# doorLock_schematic.net
KiCad netlist of a schematic drawn in Altium Designer
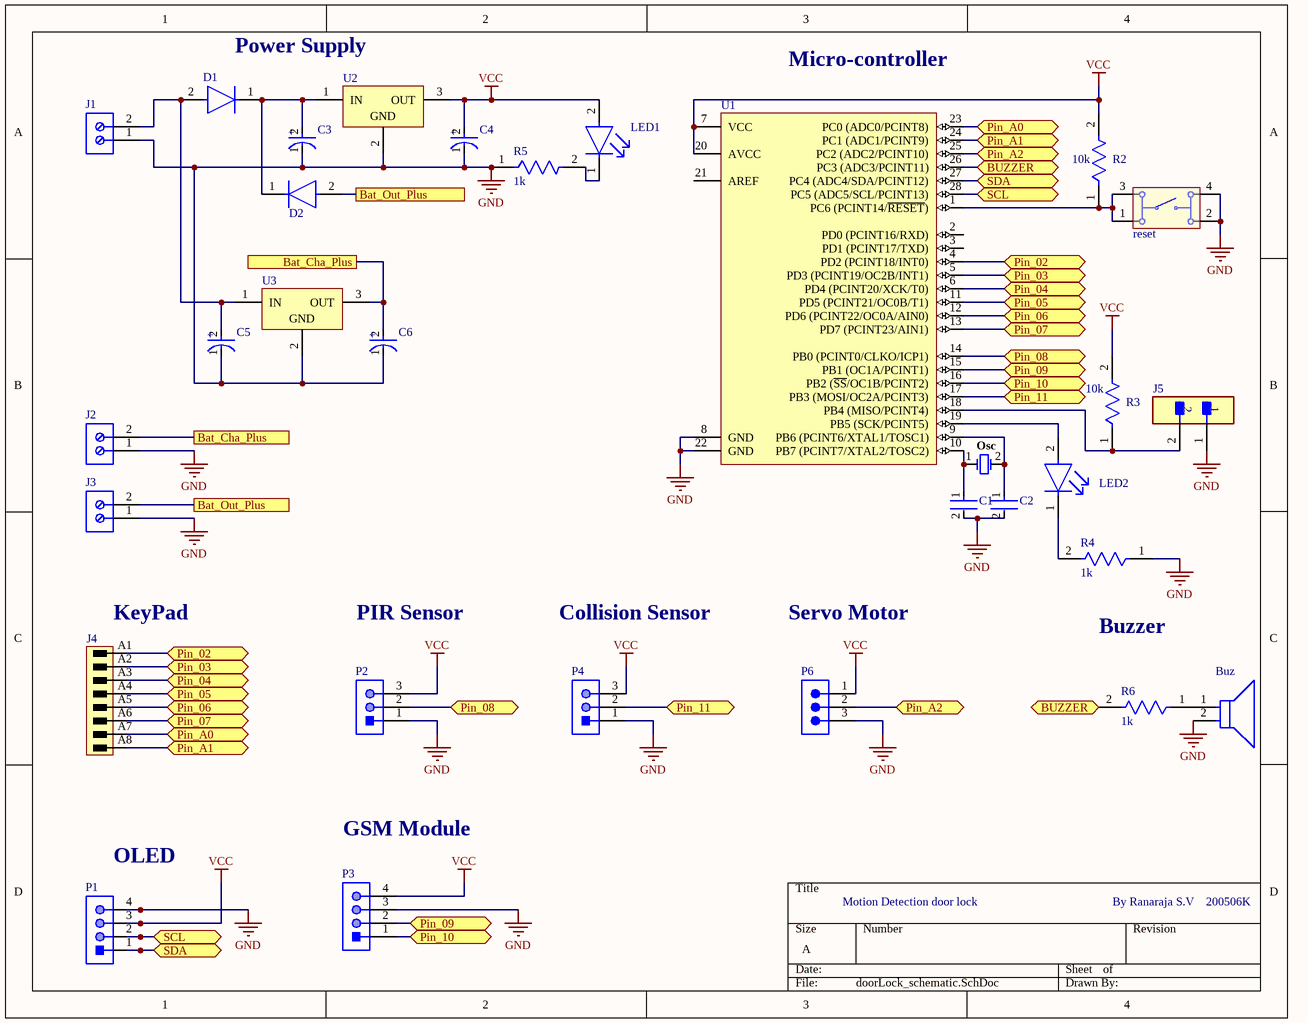
[diagram p0: doorLock_schematic.SchDoc]

(export (version "E")
  (design (tool "Eeschema 10.0.6"))
  (components
    (comp (ref "Buz")
      (value "SD1614TT-B3M")
      (footprint "FP-SD1614TT-B3M-MFG")
      (description "AUDIO MAGNETIC XDCR 6-16V TH")
      (libsource (lib "Altium Content Vault") (part "1973c4b650225fd2ddacaff6b763965"))
    )
    (comp (ref "C1")
      (value "RCE5C2A220J0DBH03A")
      (footprint "FP-RCE0DB-MFG")
      (description "Cap Ceramic 22pF 100V C0G ±5% Radial 2.5mm +125°C Ammo Pack")
      (fields (field (name "VOLTAGE") "100V") (field (name "TOLERANCE") "5%"))
      (libsource (lib "Altium Content Vault") (part "b4654b650e69147ec39a6b967a45e02"))
    )
    (comp (ref "C2")
      (value "RCE5C2A220J0DBH03A")
      (footprint "FP-RCE0DB-MFG")
      (description "Cap Ceramic 22pF 100V C0G ±5% Radial 2.5mm +125°C Ammo Pack")
      (fields (field (name "VOLTAGE") "100V") (field (name "TOLERANCE") "5%"))
      (libsource (lib "Altium Content Vault") (part "b4654b650e69147ec39a6b967a45e02"))
    )
    (comp (ref "C3")
      (value "EEUFC1V151")
      (footprint "FP-RAD-TH-D_8_0_5-L_11_5-MFG")
      (description "Aluminum Electrolytic Capacitors (Radial Lead Type) AEC-Q200 Qualified 150uF ±20% 35V")
      (fields (field (name "VOLTAGE") "35V") (field (name "TOLERANCE") "20%"))
      (libsource (lib "Altium Content Vault") (part "203bc49f2ac43e59fd269a8c329ed05"))
    )
    (comp (ref "C4")
      (value "EEUFC1V151")
      (footprint "FP-RAD-TH-D_8_0_5-L_11_5-MFG")
      (description "Aluminum Electrolytic Capacitors (Radial Lead Type) AEC-Q200 Qualified 150uF ±20% 35V")
      (fields (field (name "VOLTAGE") "35V") (field (name "TOLERANCE") "20%"))
      (libsource (lib "Altium Content Vault") (part "203bc49f2ac43e59fd269a8c329ed05"))
    )
    (comp (ref "C5")
      (value "EEUFC1V151")
      (footprint "FP-RAD-TH-D_8_0_5-L_11_5-MFG")
      (description "Aluminum Electrolytic Capacitors (Radial Lead Type) AEC-Q200 Qualified 150uF ±20% 35V")
      (fields (field (name "VOLTAGE") "35V") (field (name "TOLERANCE") "20%"))
      (libsource (lib "Altium Content Vault") (part "203bc49f2ac43e59fd269a8c329ed05"))
    )
    (comp (ref "C6")
      (value "EEUFC1V151")
      (footprint "FP-RAD-TH-D_8_0_5-L_11_5-MFG")
      (description "Aluminum Electrolytic Capacitors (Radial Lead Type) AEC-Q200 Qualified 150uF ±20% 35V")
      (fields (field (name "VOLTAGE") "35V") (field (name "TOLERANCE") "20%"))
      (libsource (lib "Altium Content Vault") (part "203bc49f2ac43e59fd269a8c329ed05"))
    )
    (comp (ref "D1")
      (value "1N4007")
      (footprint "FP-1N4007-MFG")
      (description "Rectifier diode 1000 V 1 A DO-41, ,")
      (fields
        (field (name "MANUFACTURER") "Diotec")
        (field (name "OCTOPART") "https://octopart.com/1n4007-diotec-4040411")
      )
      (libsource (lib "Altium Content Vault") (part "d7152d700b627762746794eb795d46e"))
    )
    (comp (ref "D2")
      (value "1N4007")
      (footprint "FP-1N4007-MFG")
      (description "Rectifier diode 1000 V 1 A DO-41, ,")
      (fields
        (field (name "MANUFACTURER") "Diotec")
        (field (name "OCTOPART") "https://octopart.com/1n4007-diotec-4040411")
      )
      (libsource (lib "Altium Content Vault") (part "d7152d700b627762746794eb795d46e"))
    )
    (comp (ref "J1")
      (value "691102710002")
      (footprint "691102710002")
      (description "Series 102 - 5.00 mm Horizontal Entry Modular with Pressure Clamp WR-TBL, 2 pin")
      (fields (field (name "MANUFACTURER") "Wurth Elektronik") (field (name "PUBLISHER") "WurthElektronik"))
      (libsource (lib "Altium Content Vault") (part "WE-CN-1P-F-TB2"))
    )
    (comp (ref "J2")
      (value "691102710002")
      (footprint "691102710002")
      (description "Series 102 - 5.00 mm Horizontal Entry Modular with Pressure Clamp WR-TBL, 2 pin")
      (fields (field (name "MANUFACTURER") "Wurth Elektronik") (field (name "PUBLISHER") "WurthElektronik"))
      (libsource (lib "Altium Content Vault") (part "WE-CN-1P-F-TB2"))
    )
    (comp (ref "J3")
      (value "691102710002")
      (footprint "691102710002")
      (description "Series 102 - 5.00 mm Horizontal Entry Modular with Pressure Clamp WR-TBL, 2 pin")
      (fields (field (name "MANUFACTURER") "Wurth Elektronik") (field (name "PUBLISHER") "WurthElektronik"))
      (libsource (lib "Altium Content Vault") (part "WE-CN-1P-F-TB2"))
    )
    (comp (ref "J4")
      (value "1842380000")
      (footprint "SL_SMT_3_5_180G_08")
      (description "OMNIMATE Signal - series BL/SL 3.50")
      (fields (field (name "MANUFACTURER") "Weidmueller"))
      (libsource (lib "Altium Content Vault") (part "Header_Male_08_1x08"))
    )
    (comp (ref "J5")
      (value "TSW-102-07-F-S")
      (footprint "FP-TSW-102-07-F-S-MFG")
      (description "CONN HEADER VERT 2POS 2.54MM")
      (libsource (lib "Altium Content Vault") (part "3bc925449376181038e59eaffc5286c"))
    )
    (comp (ref "LED1")
      (value "LG L29K-G2J1-24-Z")
      (footprint "FP-LG_L29K-MFG")
      (description "LED GREEN DIFFUSED 0603 SMD")
      (libsource (lib "Altium Content Vault") (part "8706943c75ba83719d021d2fdc84c58"))
    )
    (comp (ref "LED2")
      (value "LG L29K-G2J1-24-Z")
      (footprint "FP-LG_L29K-MFG")
      (description "LED GREEN DIFFUSED 0603 SMD")
      (libsource (lib "Altium Content Vault") (part "8706943c75ba83719d021d2fdc84c58"))
    )
    (comp (ref "Osc")
      (value "FOXSLF/160-20")
      (footprint "FOX-FOXSLF160-20")
      (description "Resistance Weld Thru-Hole Crystal, 16 MHz, -20 to 70 degC, 2-Pin THD, RoHS, Bulk")
      (fields (field (name "TOLERANCE") "1%"))
      (libsource (lib "Altium Content Vault") (part "XTAL-1-2-2"))
    )
    (comp (ref "P1")
      (value "691311700104")
      (footprint "691311700104")
      (description "Serie 3117 - 5.00mm Close Vertical PCB Header WR-TBL, 4 pin")
      (fields (field (name "MANUFACTURER") "Wurth Elektronik") (field (name "PUBLISHER") "WurthElektronik"))
      (libsource (lib "Altium Content Vault") (part "WE-CN-1P-M-R4"))
    )
    (comp (ref "P2")
      (value "691322110003")
      (footprint "691322110003")
      (description "Serie 3221 - 3.50mm Horizontal PCB Header WR-TBL, 3 pin")
      (fields (field (name "MANUFACTURER") "Wurth Elektronik") (field (name "PUBLISHER") "WurthElektronik"))
      (libsource (lib "Altium Content Vault") (part "WE-CN-1P-M-R3"))
    )
    (comp (ref "P3")
      (value "691311700104")
      (footprint "691311700104")
      (description "Serie 3117 - 5.00mm Close Vertical PCB Header WR-TBL, 4 pin")
      (fields (field (name "MANUFACTURER") "Wurth Elektronik") (field (name "PUBLISHER") "WurthElektronik"))
      (libsource (lib "Altium Content Vault") (part "WE-CN-1P-M-R4"))
    )
    (comp (ref "P4")
      (value "691322110003")
      (footprint "691322110003")
      (description "Serie 3221 - 3.50mm Horizontal PCB Header WR-TBL, 3 pin")
      (fields (field (name "MANUFACTURER") "Wurth Elektronik") (field (name "PUBLISHER") "WurthElektronik"))
      (libsource (lib "Altium Content Vault") (part "WE-CN-1P-M-R3"))
    )
    (comp (ref "P6")
      (value "TSW-103-07-G-S")
      (footprint "SMTC-TSW-103-07-X-S")
      (description "0.025\" SQ Post Header, Through-hole, Vertical, -55 to 125 degC, 2.54 mm Pitch, 3-Pin, Male, RoHS")
      (fields (field (name "MANUFACTURER") "Samtec"))
      (libsource (lib "Altium Content Vault") (part "SMTC-TSW-103-X-X-S-X"))
    )
    (comp (ref "R2")
      (value "MRS16000C2002FCT00")
      (footprint "FP-MRS1600-MFG")
      (description "RES 20K OHM 0.4W 1% AXIAL")
      (fields (field (name "TOLERANCE") "1%") (field (name "RESISTANCE") "10k"))
      (libsource (lib "Altium Content Vault") (part "1029c3af85768c4190bb7ad29bc67b5"))
    )
    (comp (ref "R3")
      (value "MRS16000C2002FCT00")
      (footprint "FP-MRS1600-MFG")
      (description "RES 20K OHM 0.4W 1% AXIAL")
      (fields (field (name "TOLERANCE") "1%") (field (name "RESISTANCE") "10k"))
      (libsource (lib "Altium Content Vault") (part "1029c3af85768c4190bb7ad29bc67b5"))
    )
    (comp (ref "R4")
      (value "MRS16000C2002FCT00")
      (footprint "FP-MRS1600-MFG")
      (description "RES 20K OHM 0.4W 1% AXIAL")
      (fields (field (name "TOLERANCE") "1%") (field (name "RESISTANCE") "1k"))
      (libsource (lib "Altium Content Vault") (part "1029c3af85768c4190bb7ad29bc67b5"))
    )
    (comp (ref "R5")
      (value "MRS16000C2002FCT00")
      (footprint "FP-MRS1600-MFG")
      (description "RES 20K OHM 0.4W 1% AXIAL")
      (fields (field (name "TOLERANCE") "1%") (field (name "RESISTANCE") "1k"))
      (libsource (lib "Altium Content Vault") (part "1029c3af85768c4190bb7ad29bc67b5"))
    )
    (comp (ref "R6")
      (value "MRS16000C2002FCT00")
      (footprint "FP-MRS1600-MFG")
      (description "RES 20K OHM 0.4W 1% AXIAL")
      (fields (field (name "TOLERANCE") "1%") (field (name "RESISTANCE") "1k"))
      (libsource (lib "Altium Content Vault") (part "1029c3af85768c4190bb7ad29bc67b5"))
    )
    (comp (ref "reset")
      (value "430156043726")
      (footprint "430156043726")
      (description "WS-TATV THT Tact Switch 6X6 mm")
      (fields (field (name "MANUFACTURER") "Wuerth Elektronik"))
      (libsource (lib "Altium Content Vault") (part "WE-TACT-SW-4"))
    )
    (comp (ref "U1")
      (value "ATmega328-PU")
      (footprint "28P3")
      (libsource (lib "Altium Content Vault") (part "MC-8B-ATM48-IL28"))
    )
    (comp (ref "U2")
      (value "L7805CV")
      (footprint "TO220")
      (description "Positive Voltage Regulator, 5V, 3-Pin TO-220")
      (libsource (lib "Altium Content Vault") (part "PM-REG-L4940-SIL3"))
    )
    (comp (ref "U3")
      (value "L7805CV")
      (footprint "TO220")
      (description "Positive Voltage Regulator, 5V, 3-Pin TO-220")
      (libsource (lib "Altium Content Vault") (part "PM-REG-L4940-SIL3"))
    )
  )
  (nets
    (net (code "1") (name "/BUZZER") (class "Default")
      (node (ref "R6") (pin "2") (pinfunction "2_2") (pintype "passive"))
      (node (ref "U1") (pin "26") (pinfunction "PC3_(ADC3/PCINT11)_26") (pintype "bidirectional"))
    )
    (net (code "2") (name "/Bat_Cha_Plus") (class "Default")
      (node (ref "C6") (pin "2") (pinfunction "A_2") (pintype "passive"))
      (node (ref "J2") (pin "2") (pinfunction "2_2") (pintype "passive"))
      (node (ref "U3") (pin "3") (pinfunction "OUT_3") (pintype "power_in"))
    )
    (net (code "3") (name "/Bat_Out_Plus") (class "Default")
      (node (ref "D2") (pin "2") (pinfunction "A_2") (pintype "passive"))
      (node (ref "J3") (pin "2") (pinfunction "2_2") (pintype "passive"))
    )
    (net (code "4") (name "/Pin_02") (class "Default")
      (node (ref "J4") (pin "A1") (pinfunction "A1_A1") (pintype "passive"))
      (node (ref "U1") (pin "4") (pinfunction "PD2_(PCINT18/INT0)_4") (pintype "bidirectional"))
    )
    (net (code "5") (name "/Pin_03") (class "Default")
      (node (ref "J4") (pin "A2") (pinfunction "A2_A2") (pintype "passive"))
      (node (ref "U1") (pin "5") (pinfunction "PD3_(PCINT19/OC2B/INT1)_5") (pintype "bidirectional"))
    )
    (net (code "6") (name "/Pin_04") (class "Default")
      (node (ref "J4") (pin "A3") (pinfunction "A3_A3") (pintype "passive"))
      (node (ref "U1") (pin "6") (pinfunction "PD4_(PCINT20/XCK/T0)_6") (pintype "bidirectional"))
    )
    (net (code "7") (name "/Pin_05") (class "Default")
      (node (ref "J4") (pin "A4") (pinfunction "A4_A4") (pintype "passive"))
      (node (ref "U1") (pin "11") (pinfunction "PD5_(PCINT21/OC0B/T1)_11") (pintype "bidirectional"))
    )
    (net (code "8") (name "/Pin_06") (class "Default")
      (node (ref "J4") (pin "A5") (pinfunction "A5_A5") (pintype "passive"))
      (node (ref "U1") (pin "12") (pinfunction "PD6_(PCINT22/OC0A/AIN0)_12") (pintype "bidirectional"))
    )
    (net (code "9") (name "/Pin_07") (class "Default")
      (node (ref "J4") (pin "A6") (pinfunction "A6_A6") (pintype "passive"))
      (node (ref "U1") (pin "13") (pinfunction "PD7_(PCINT23/AIN1)_13") (pintype "bidirectional"))
    )
    (net (code "10") (name "/Pin_08") (class "Default")
      (node (ref "P2") (pin "2") (pinfunction "2_2") (pintype "passive"))
      (node (ref "U1") (pin "14") (pinfunction "PB0_(PCINT0/CLKO/ICP1)_14") (pintype "bidirectional"))
    )
    (net (code "11") (name "/Pin_09") (class "Default")
      (node (ref "P3") (pin "2") (pinfunction "2_2") (pintype "passive"))
      (node (ref "U1") (pin "15") (pinfunction "PB1_(OC1A/PCINT1)_15") (pintype "bidirectional"))
    )
    (net (code "12") (name "/Pin_10") (class "Default")
      (node (ref "P3") (pin "1") (pinfunction "1_1") (pintype "passive"))
      (node (ref "U1") (pin "16") (pinfunction "PB2_(~{SS}/OC1B/PCINT2)_16") (pintype "bidirectional"))
    )
    (net (code "13") (name "/Pin_11") (class "Default")
      (node (ref "P4") (pin "2") (pinfunction "2_2") (pintype "passive"))
      (node (ref "U1") (pin "17") (pinfunction "PB3_(MOSI/OC2A/PCINT3)_17") (pintype "bidirectional"))
    )
    (net (code "14") (name "/Pin_A0") (class "Default")
      (node (ref "J4") (pin "A7") (pinfunction "A7_A7") (pintype "passive"))
      (node (ref "U1") (pin "23") (pinfunction "PC0_(ADC0/PCINT8)_23") (pintype "bidirectional"))
    )
    (net (code "15") (name "/Pin_A1") (class "Default")
      (node (ref "J4") (pin "A8") (pinfunction "A8_A8") (pintype "passive"))
      (node (ref "U1") (pin "24") (pinfunction "PC1_(ADC1/PCINT9)_24") (pintype "bidirectional"))
    )
    (net (code "16") (name "/Pin_A2") (class "Default")
      (node (ref "P6") (pin "2") (pinfunction "2_2") (pintype "passive"))
      (node (ref "U1") (pin "25") (pinfunction "PC2_(ADC2/PCINT10)_25") (pintype "bidirectional"))
    )
    (net (code "17") (name "/SCL") (class "Default")
      (node (ref "P1") (pin "2") (pinfunction "2_2") (pintype "passive"))
      (node (ref "U1") (pin "28") (pinfunction "PC5_(ADC5/SCL/PCINT13)_28") (pintype "bidirectional"))
    )
    (net (code "18") (name "/SDA") (class "Default")
      (node (ref "P1") (pin "1") (pinfunction "1_1") (pintype "passive"))
      (node (ref "U1") (pin "27") (pinfunction "PC4_(ADC4/SDA/PCINT12)_27") (pintype "bidirectional"))
    )
    (net (code "19") (name "GND") (class "Default")
      (node (ref "Buz") (pin "2") (pinfunction "A_2") (pintype "passive"))
      (node (ref "C1") (pin "2") (pinfunction "2_2") (pintype "passive"))
      (node (ref "C2") (pin "2") (pinfunction "2_2") (pintype "passive"))
      (node (ref "C3") (pin "1") (pinfunction "C_1") (pintype "passive"))
      (node (ref "C4") (pin "1") (pinfunction "C_1") (pintype "passive"))
      (node (ref "C5") (pin "1") (pinfunction "C_1") (pintype "passive"))
      (node (ref "C6") (pin "1") (pinfunction "C_1") (pintype "passive"))
      (node (ref "J1") (pin "1") (pinfunction "1_1") (pintype "passive"))
      (node (ref "J2") (pin "1") (pinfunction "1_1") (pintype "passive"))
      (node (ref "J3") (pin "1") (pinfunction "1_1") (pintype "passive"))
      (node (ref "J5") (pin "1") (pinfunction "1_1") (pintype "passive"))
      (node (ref "P1") (pin "4") (pinfunction "4_4") (pintype "passive"))
      (node (ref "P2") (pin "1") (pinfunction "1_1") (pintype "passive"))
      (node (ref "P3") (pin "3") (pinfunction "3_3") (pintype "passive"))
      (node (ref "P4") (pin "1") (pinfunction "1_1") (pintype "passive"))
      (node (ref "P6") (pin "3") (pinfunction "3_3") (pintype "passive"))
      (node (ref "R4") (pin "1") (pinfunction "1_1") (pintype "passive"))
      (node (ref "R5") (pin "1") (pinfunction "1_1") (pintype "passive"))
      (node (ref "U1") (pin "22") (pinfunction "GND_22") (pintype "power_in"))
      (node (ref "U1") (pin "8") (pinfunction "GND_8") (pintype "power_in"))
      (node (ref "U2") (pin "2") (pinfunction "GND_2") (pintype "power_in"))
      (node (ref "U3") (pin "2") (pinfunction "GND_2") (pintype "power_in"))
      (node (ref "reset") (pin "2") (pinfunction "2_2") (pintype "passive"))
      (node (ref "reset") (pin "4") (pinfunction "4_4") (pintype "passive"))
    )
    (net (code "20") (name "Net-(Buz-C)") (class "Default")
      (node (ref "Buz") (pin "1") (pinfunction "C_1") (pintype "passive"))
      (node (ref "R6") (pin "1") (pinfunction "1_1") (pintype "passive"))
    )
    (net (code "21") (name "Net-(C3-A)") (class "Default")
      (node (ref "C3") (pin "2") (pinfunction "A_2") (pintype "passive"))
      (node (ref "D1") (pin "1") (pinfunction "C_1") (pintype "passive"))
      (node (ref "D2") (pin "1") (pinfunction "C_1") (pintype "passive"))
      (node (ref "U2") (pin "1") (pinfunction "IN_1") (pintype "power_in"))
    )
    (net (code "22") (name "Net-(C5-A)") (class "Default")
      (node (ref "C5") (pin "2") (pinfunction "A_2") (pintype "passive"))
      (node (ref "D1") (pin "2") (pinfunction "A_2") (pintype "passive"))
      (node (ref "J1") (pin "2") (pinfunction "2_2") (pintype "passive"))
      (node (ref "U3") (pin "1") (pinfunction "IN_1") (pintype "power_in"))
    )
    (net (code "23") (name "Net-(LED1-C)") (class "Default")
      (node (ref "LED1") (pin "1") (pinfunction "C_1") (pintype "passive"))
      (node (ref "R5") (pin "2") (pinfunction "2_2") (pintype "passive"))
    )
    (net (code "24") (name "Net-(LED2-A)") (class "Default")
      (node (ref "LED2") (pin "2") (pinfunction "A_2") (pintype "passive"))
      (node (ref "U1") (pin "19") (pinfunction "PB5_(SCK/PCINT5)_19") (pintype "bidirectional"))
    )
    (net (code "25") (name "Net-(LED2-C)") (class "Default")
      (node (ref "LED2") (pin "1") (pinfunction "C_1") (pintype "passive"))
      (node (ref "R4") (pin "2") (pinfunction "2_2") (pintype "passive"))
    )
    (net (code "26") (name "Net-(U1-PB4_(MISO{slash}PCINT4))") (class "Default")
      (node (ref "J5") (pin "2") (pinfunction "2_2") (pintype "passive"))
      (node (ref "R3") (pin "1") (pinfunction "1_1") (pintype "passive"))
      (node (ref "U1") (pin "18") (pinfunction "PB4_(MISO/PCINT4)_18") (pintype "bidirectional"))
    )
    (net (code "27") (name "Net-(U1-PB6_(PCINT6{slash}XTAL1{slash}TOSC1))") (class "Default")
      (node (ref "C2") (pin "1") (pinfunction "1_1") (pintype "passive"))
      (node (ref "Osc") (pin "2") (pinfunction "2_2") (pintype "passive"))
      (node (ref "U1") (pin "9") (pinfunction "PB6_(PCINT6/XTAL1/TOSC1)_9") (pintype "bidirectional"))
    )
    (net (code "28") (name "Net-(U1-PB7_(PCINT7{slash}XTAL2{slash}TOSC2))") (class "Default")
      (node (ref "C1") (pin "1") (pinfunction "1_1") (pintype "passive"))
      (node (ref "Osc") (pin "1") (pinfunction "1_1") (pintype "passive"))
      (node (ref "U1") (pin "10") (pinfunction "PB7_(PCINT7/XTAL2/TOSC2)_10") (pintype "bidirectional"))
    )
    (net (code "29") (name "Net-(U1-PC6_(PCINT14{slash}~{RESET}))") (class "Default")
      (node (ref "R2") (pin "1") (pinfunction "1_1") (pintype "passive"))
      (node (ref "U1") (pin "1") (pinfunction "PC6_(PCINT14/~{RESET})_1") (pintype "bidirectional"))
      (node (ref "reset") (pin "1") (pinfunction "1_1") (pintype "passive"))
      (node (ref "reset") (pin "3") (pinfunction "3_3") (pintype "passive"))
    )
    (net (code "30") (name "VCC") (class "Default")
      (node (ref "C4") (pin "2") (pinfunction "A_2") (pintype "passive"))
      (node (ref "LED1") (pin "2") (pinfunction "A_2") (pintype "passive"))
      (node (ref "P1") (pin "3") (pinfunction "3_3") (pintype "passive"))
      (node (ref "P2") (pin "3") (pinfunction "3_3") (pintype "passive"))
      (node (ref "P3") (pin "4") (pinfunction "4_4") (pintype "passive"))
      (node (ref "P4") (pin "3") (pinfunction "3_3") (pintype "passive"))
      (node (ref "P6") (pin "1") (pinfunction "1_1") (pintype "passive"))
      (node (ref "R2") (pin "2") (pinfunction "2_2") (pintype "passive"))
      (node (ref "R3") (pin "2") (pinfunction "2_2") (pintype "passive"))
      (node (ref "U1") (pin "20") (pinfunction "AVCC_20") (pintype "power_in"))
      (node (ref "U1") (pin "7") (pinfunction "VCC_7") (pintype "power_in"))
      (node (ref "U2") (pin "3") (pinfunction "OUT_3") (pintype "power_in"))
    )
    (net (code "31") (name "unconnected-(U1-AREF-Pad21)") (class "Default")
      (node (ref "U1") (pin "21") (pinfunction "AREF_21") (pintype "power_in"))
    )
    (net (code "32") (name "unconnected-(U1-PD0_(PCINT16{slash}RXD)-Pad2)") (class "Default")
      (node (ref "U1") (pin "2") (pinfunction "PD0_(PCINT16/RXD)_2") (pintype "bidirectional"))
    )
    (net (code "33") (name "unconnected-(U1-PD1_(PCINT17{slash}TXD)-Pad3)") (class "Default")
      (node (ref "U1") (pin "3") (pinfunction "PD1_(PCINT17/TXD)_3") (pintype "bidirectional"))
    )
  )
)
